# MotionerController.net
KiCad netlist of a schematic drawn in EAGLE
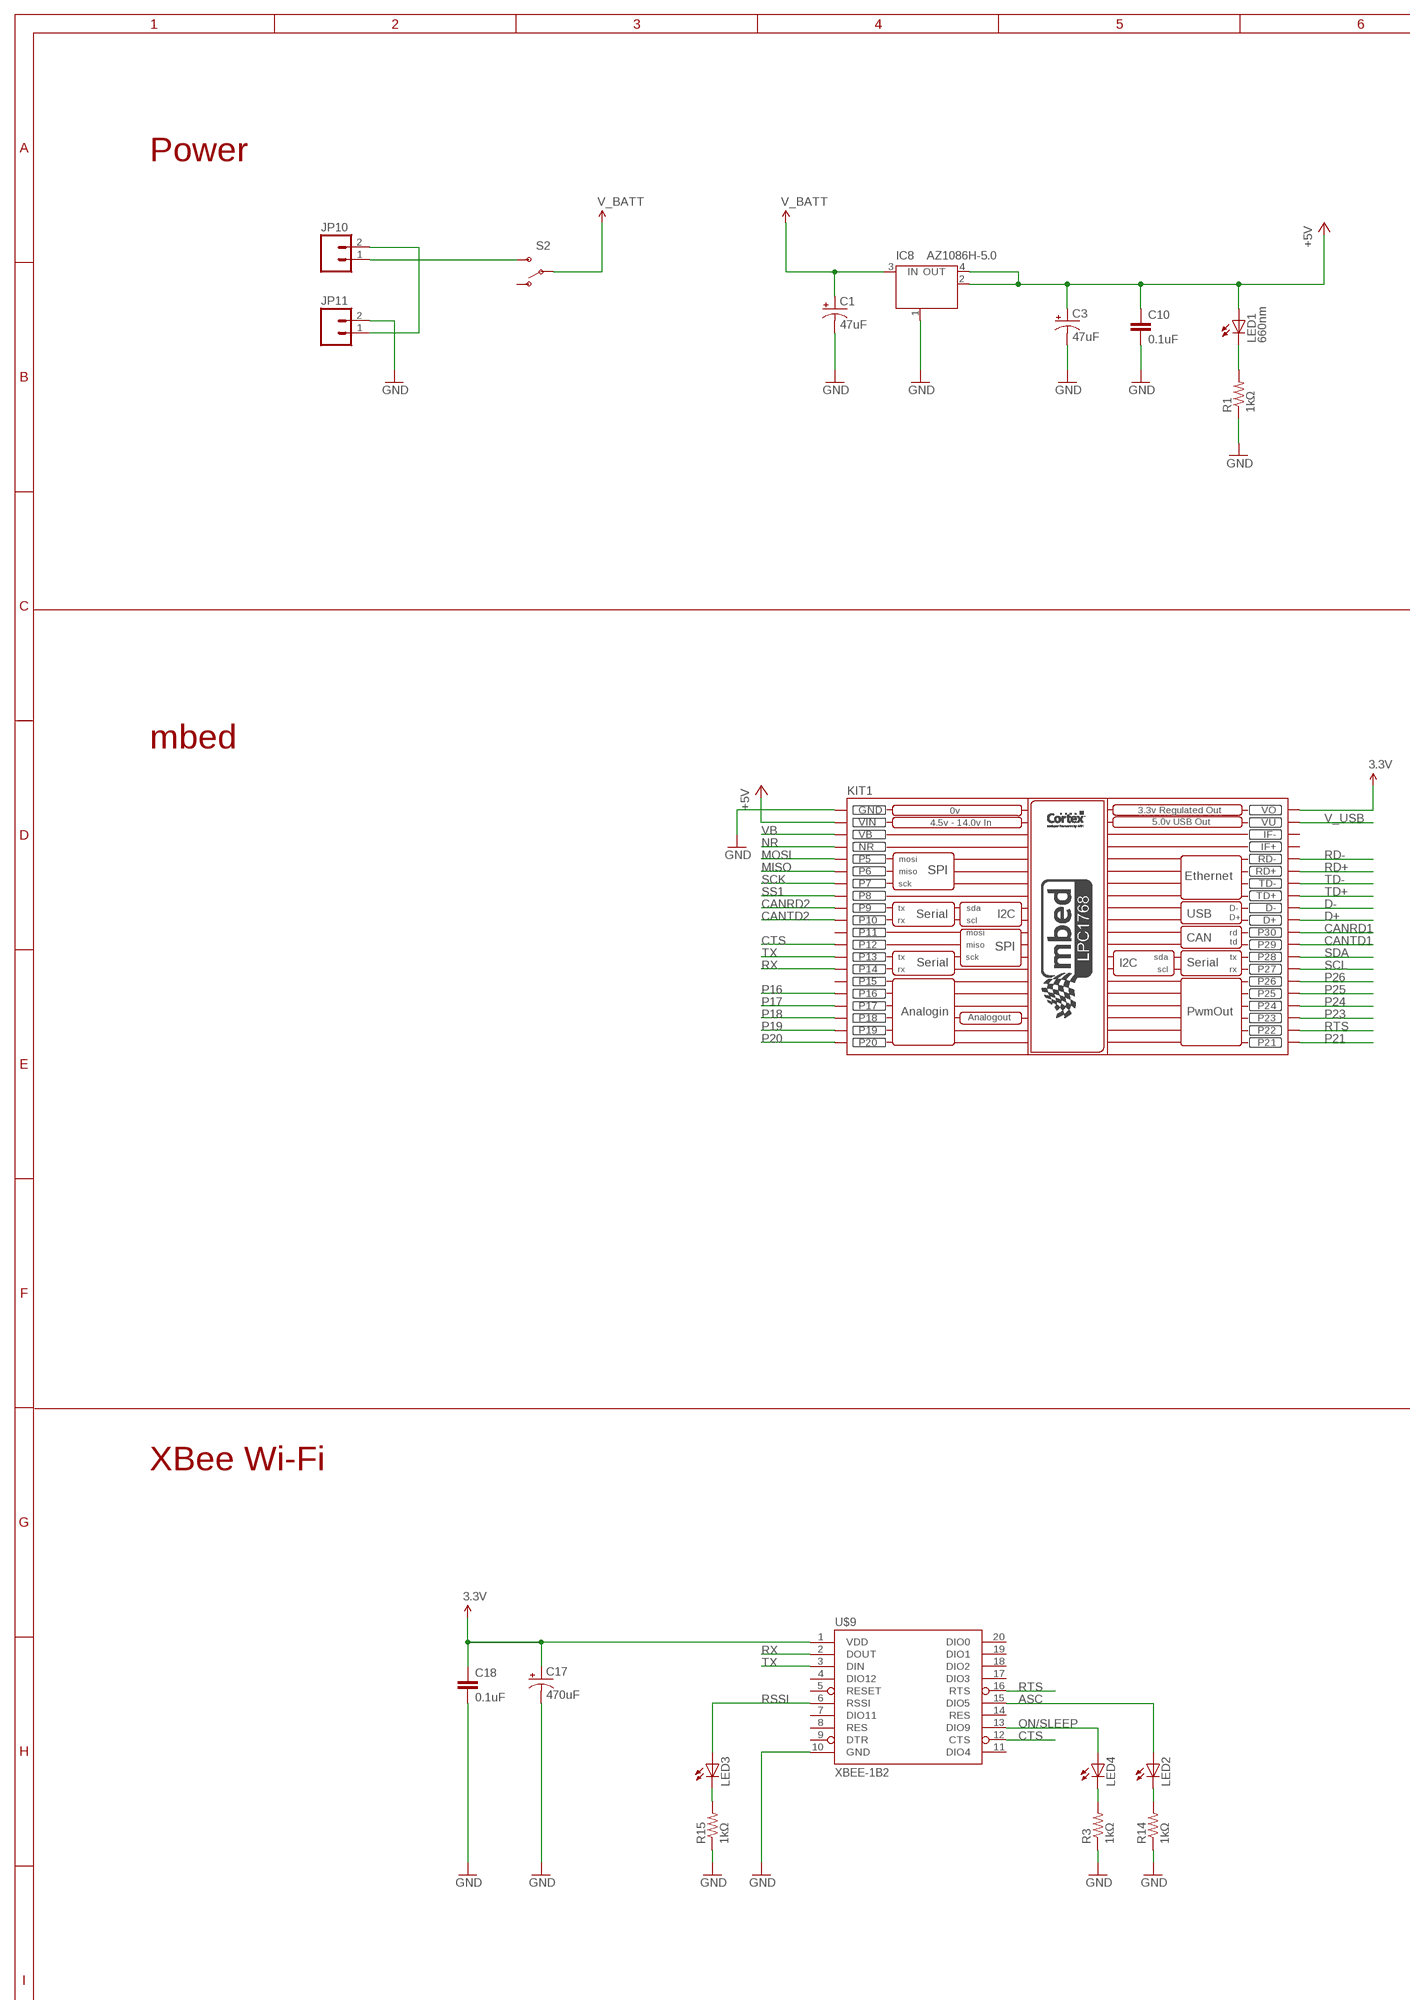
[diagram p0: schematic, sheet 1, part 1 of 2]
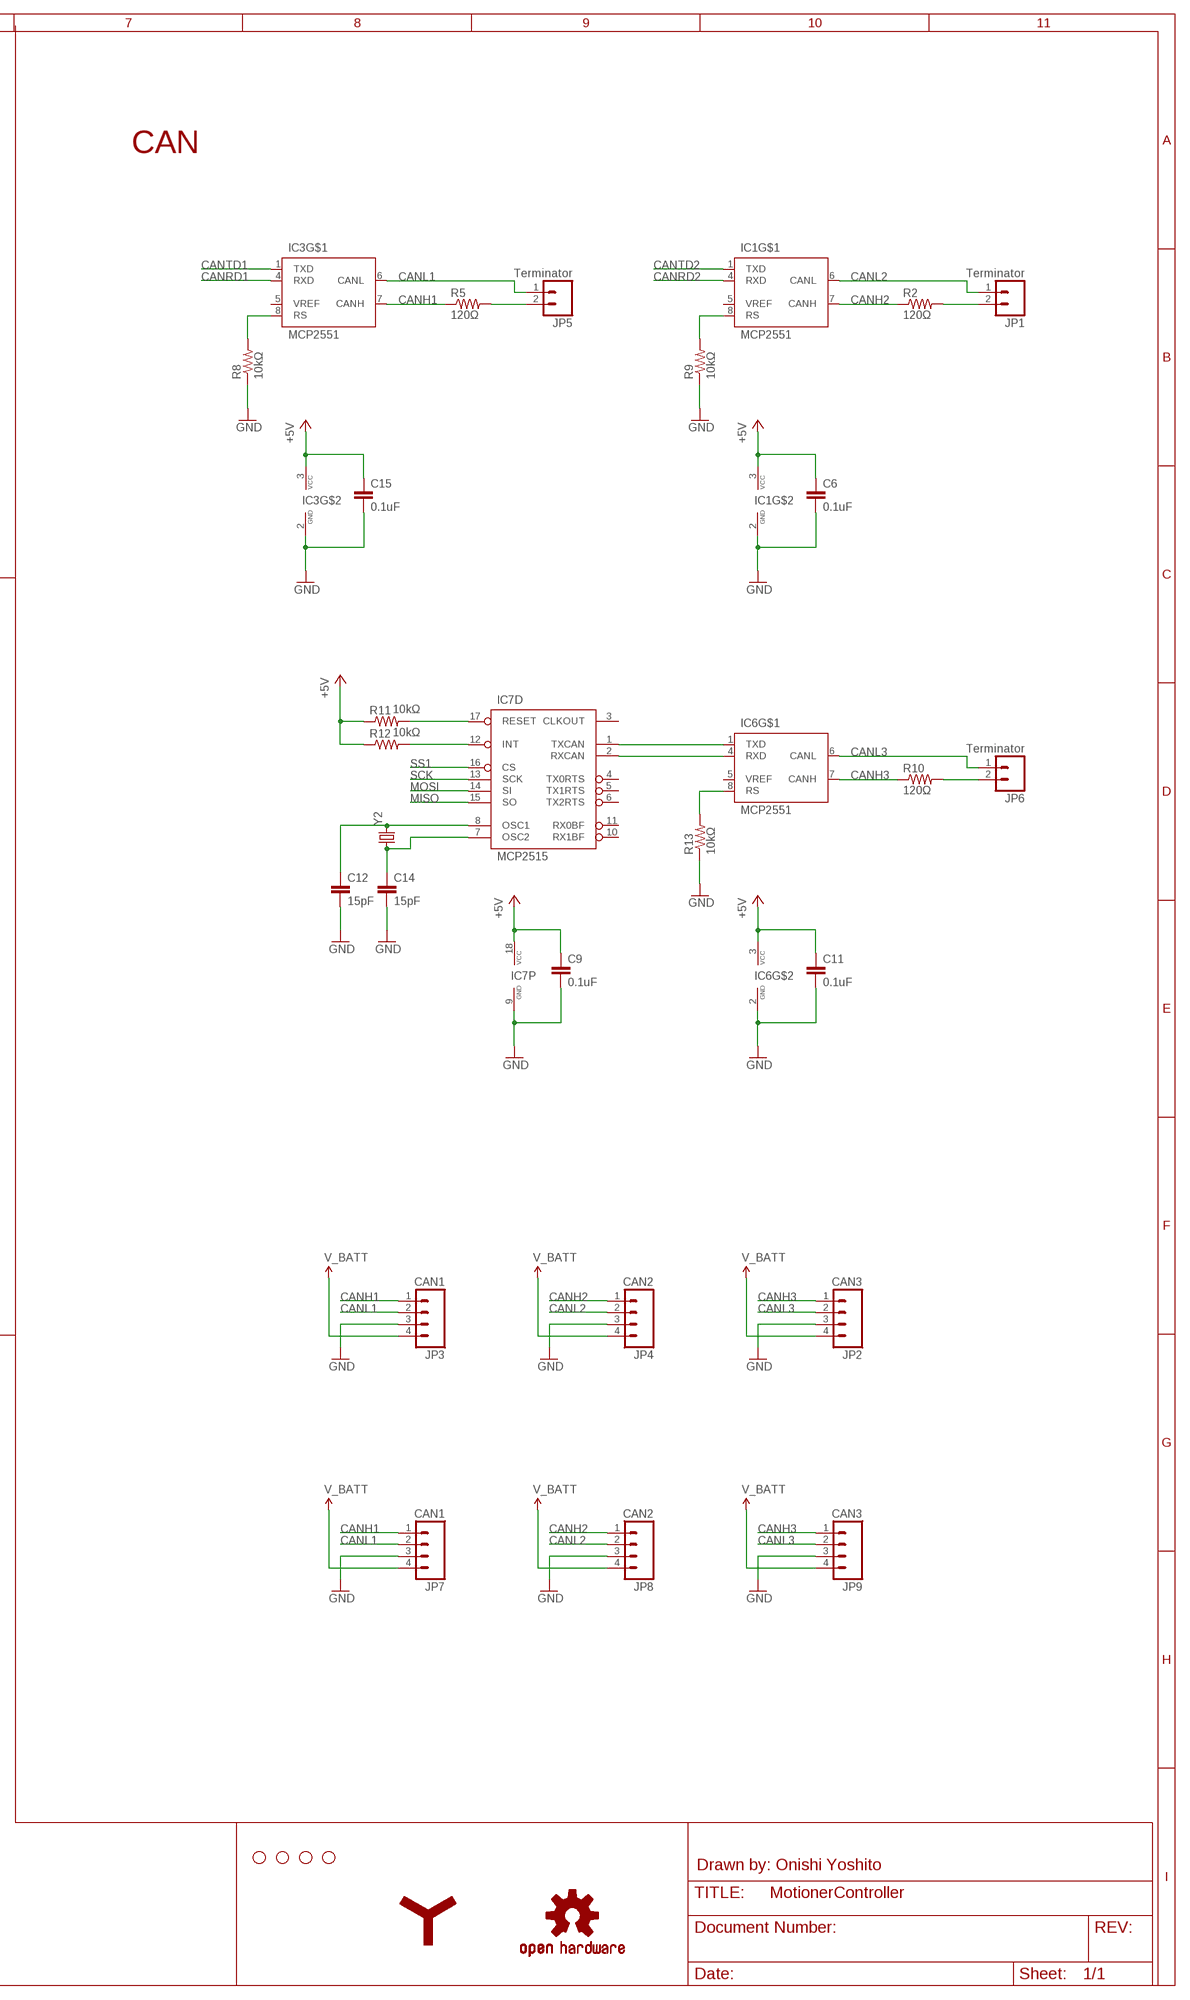
[diagram p1: schematic, sheet 1, part 2 of 2]

(export (version "E")
  (design (tool "Eeschema 10.0.6"))
  (components
    (comp (ref "C1")
      (value "47uF")
      (footprint "eagle-import:PANASONIC_D")
      (libsource (lib "eagle-import") (part "CAP_POLD"))
    )
    (comp (ref "C3")
      (value "47uF")
      (footprint "eagle-import:PANASONIC_D")
      (libsource (lib "eagle-import") (part "CAP_POLD"))
    )
    (comp (ref "C6")
      (value "0.1uF")
      (footprint "eagle-import:0603-CAP")
      (libsource (lib "eagle-import") (part "CAP0603-CAP"))
    )
    (comp (ref "C9")
      (value "0.1uF")
      (footprint "eagle-import:0603-CAP")
      (libsource (lib "eagle-import") (part "CAP0603-CAP"))
    )
    (comp (ref "C10")
      (value "0.1uF")
      (footprint "eagle-import:0603-CAP")
      (libsource (lib "eagle-import") (part "CAP0603-CAP"))
    )
    (comp (ref "C11")
      (value "0.1uF")
      (footprint "eagle-import:0603-CAP")
      (libsource (lib "eagle-import") (part "CAP0603-CAP"))
    )
    (comp (ref "C12")
      (value "15pF")
      (footprint "eagle-import:0603-CAP")
      (libsource (lib "eagle-import") (part "CAP0603-CAP"))
    )
    (comp (ref "C14")
      (value "15pF")
      (footprint "eagle-import:0603-CAP")
      (libsource (lib "eagle-import") (part "CAP0603-CAP"))
    )
    (comp (ref "C15")
      (value "0.1uF")
      (footprint "eagle-import:0603-CAP")
      (libsource (lib "eagle-import") (part "CAP0603-CAP"))
    )
    (comp (ref "C17")
      (value "470uF")
      (footprint "eagle-import:PANASONIC_G")
      (libsource (lib "eagle-import") (part "CAP_POLG"))
    )
    (comp (ref "C18")
      (value "0.1uF")
      (footprint "eagle-import:0603-CAP")
      (libsource (lib "eagle-import") (part "CAP0603-CAP"))
    )
    (comp (ref "IC1")
      (value "MCP2551")
      (footprint "eagle-import:SO08")
      (libsource (lib "eagle-import") (part "MCP2551SO8"))
    )
    (comp (ref "IC3")
      (value "MCP2551")
      (footprint "eagle-import:SO08")
      (libsource (lib "eagle-import") (part "MCP2551SO8"))
    )
    (comp (ref "IC6")
      (value "MCP2551")
      (footprint "eagle-import:SO08")
      (libsource (lib "eagle-import") (part "MCP2551SO8"))
    )
    (comp (ref "IC7")
      (value "MCP2515")
      (footprint "eagle-import:SO-18W")
      (libsource (lib "eagle-import") (part "MCP2515SO"))
    )
    (comp (ref "IC8")
      (value "AZ1086H-5.0")
      (footprint "eagle-import:SOT223")
      (libsource (lib "eagle-import") (part "MC33269ST-3.3T3"))
    )
    (comp (ref "JP1")
      (value "Terminator")
      (footprint "eagle-import:1X02")
      (libsource (lib "eagle-import") (part "M02PTH"))
    )
    (comp (ref "JP2")
      (value "CAN3")
      (footprint "eagle-import:JST-4-PTH")
      (libsource (lib "eagle-import") (part "M04JST-PTH"))
    )
    (comp (ref "JP3")
      (value "CAN1")
      (footprint "eagle-import:JST-4-PTH")
      (libsource (lib "eagle-import") (part "M04JST-PTH"))
    )
    (comp (ref "JP4")
      (value "CAN2")
      (footprint "eagle-import:JST-4-PTH")
      (libsource (lib "eagle-import") (part "M04JST-PTH"))
    )
    (comp (ref "JP5")
      (value "Terminator")
      (footprint "eagle-import:1X02")
      (libsource (lib "eagle-import") (part "M02PTH"))
    )
    (comp (ref "JP6")
      (value "Terminator")
      (footprint "eagle-import:1X02")
      (libsource (lib "eagle-import") (part "M02PTH"))
    )
    (comp (ref "JP7")
      (value "CAN1")
      (footprint "eagle-import:JST-4-PTH")
      (libsource (lib "eagle-import") (part "M04JST-PTH"))
    )
    (comp (ref "JP8")
      (value "CAN2")
      (footprint "eagle-import:JST-4-PTH")
      (libsource (lib "eagle-import") (part "M04JST-PTH"))
    )
    (comp (ref "JP9")
      (value "CAN3")
      (footprint "eagle-import:JST-4-PTH")
      (libsource (lib "eagle-import") (part "M04JST-PTH"))
    )
    (comp (ref "JP10")
      (value "M02JST-PTH-2")
      (footprint "eagle-import:JST-2-PTH")
      (libsource (lib "eagle-import") (part "M02JST-PTH-2"))
    )
    (comp (ref "JP11")
      (value "M02JST-PTH-2")
      (footprint "eagle-import:JST-2-PTH")
      (libsource (lib "eagle-import") (part "M02JST-PTH-2"))
    )
    (comp (ref "JP12")
      (value "STAND-OFF")
      (footprint "eagle-import:STAND-OFF")
      (libsource (lib "eagle-import") (part "STAND-OFF"))
    )
    (comp (ref "JP13")
      (value "STAND-OFF")
      (footprint "eagle-import:STAND-OFF")
      (libsource (lib "eagle-import") (part "STAND-OFF"))
    )
    (comp (ref "JP15")
      (value "STAND-OFF")
      (footprint "eagle-import:STAND-OFF")
      (libsource (lib "eagle-import") (part "STAND-OFF"))
    )
    (comp (ref "JP16")
      (value "STAND-OFF")
      (footprint "eagle-import:STAND-OFF")
      (libsource (lib "eagle-import") (part "STAND-OFF"))
    )
    (comp (ref "KIT1")
      (value "MBED_NXP_LPC1768")
      (footprint "eagle-import:MBED-KIT")
      (libsource (lib "eagle-import") (part "MBED_NXP_LPC1768"))
    )
    (comp (ref "LED1")
      (value "660nm")
      (footprint "eagle-import:LED-0603")
      (libsource (lib "eagle-import") (part "LED0603"))
    )
    (comp (ref "LED2")
      (value "LED0603")
      (footprint "eagle-import:LED-0603")
      (libsource (lib "eagle-import") (part "LED0603"))
    )
    (comp (ref "LED3")
      (value "LED0603")
      (footprint "eagle-import:LED-0603")
      (libsource (lib "eagle-import") (part "LED0603"))
    )
    (comp (ref "LED4")
      (value "LED0603")
      (footprint "eagle-import:LED-0603")
      (libsource (lib "eagle-import") (part "LED0603"))
    )
    (comp (ref "R1")
      (value "1kΩ")
      (footprint "eagle-import:0603-RES")
      (libsource (lib "eagle-import") (part "RESISTOR0603-RES"))
    )
    (comp (ref "R2")
      (value "120Ω")
      (footprint "eagle-import:0603-RES")
      (libsource (lib "eagle-import") (part "RESISTOR0603-RES"))
    )
    (comp (ref "R3")
      (value "1kΩ")
      (footprint "eagle-import:0603-RES")
      (libsource (lib "eagle-import") (part "RESISTOR0603-RES"))
    )
    (comp (ref "R5")
      (value "120Ω")
      (footprint "eagle-import:0603-RES")
      (libsource (lib "eagle-import") (part "RESISTOR0603-RES"))
    )
    (comp (ref "R8")
      (value "10kΩ")
      (footprint "eagle-import:0603-RES")
      (libsource (lib "eagle-import") (part "RESISTOR0603-RES"))
    )
    (comp (ref "R9")
      (value "10kΩ")
      (footprint "eagle-import:0603-RES")
      (libsource (lib "eagle-import") (part "RESISTOR0603-RES"))
    )
    (comp (ref "R10")
      (value "120Ω")
      (footprint "eagle-import:0603-RES")
      (libsource (lib "eagle-import") (part "RESISTOR0603-RES"))
    )
    (comp (ref "R11")
      (value "10kΩ")
      (footprint "eagle-import:0603-RES")
      (libsource (lib "eagle-import") (part "RESISTOR0603-RES"))
    )
    (comp (ref "R12")
      (value "10kΩ")
      (footprint "eagle-import:0603-RES")
      (libsource (lib "eagle-import") (part "RESISTOR0603-RES"))
    )
    (comp (ref "R13")
      (value "10kΩ")
      (footprint "eagle-import:0603-RES")
      (libsource (lib "eagle-import") (part "RESISTOR0603-RES"))
    )
    (comp (ref "R14")
      (value "1kΩ")
      (footprint "eagle-import:0603-RES")
      (libsource (lib "eagle-import") (part "RESISTOR0603-RES"))
    )
    (comp (ref "R15")
      (value "1kΩ")
      (footprint "eagle-import:0603-RES")
      (libsource (lib "eagle-import") (part "RESISTOR0603-RES"))
    )
    (comp (ref "S2")
      (value "SWITCH-SPDTPTH")
      (footprint "eagle-import:SWITCH-SPDT")
      (libsource (lib "eagle-import") (part "SWITCH-SPDTPTH"))
    )
    (comp (ref "U$9")
      (value "XBEE-1B2")
      (footprint "eagle-import:XBEE-SILK")
      (libsource (lib "eagle-import") (part "XBEE-1B2"))
    )
    (comp (ref "U$10")
      (value "YCAM_LOGO_L")
      (footprint "eagle-import:YCAM_LOGO_L")
      (libsource (lib "eagle-import") (part "YCAM_LOGO_L"))
    )
    (comp (ref "U$12")
      (value "OSHW-LOGOL")
      (footprint "eagle-import:OSHW-LOGO-L")
      (libsource (lib "eagle-import") (part "OSHW-LOGOL"))
    )
    (comp (ref "Y2")
      (value "CRYSTAL5X3")
      (footprint "eagle-import:CRYSTAL-SMD-5X3")
      (libsource (lib "eagle-import") (part "CRYSTAL5X3"))
    )
  )
  (nets
    (net (code "1") (name "+5V") (class "Default")
      (node (ref "C10") (pin "1") (pinfunction "1_1") (pintype "passive"))
      (node (ref "C11") (pin "1") (pinfunction "1_1") (pintype "passive"))
      (node (ref "C15") (pin "1") (pinfunction "1_1") (pintype "passive"))
      (node (ref "C3") (pin "+") (pinfunction "+_+") (pintype "passive"))
      (node (ref "C6") (pin "1") (pinfunction "1_1") (pintype "passive"))
      (node (ref "C9") (pin "1") (pinfunction "1_1") (pintype "passive"))
      (node (ref "IC1") (pin "3") (pinfunction "VCC_3") (pintype "power_in"))
      (node (ref "IC3") (pin "3") (pinfunction "VCC_3") (pintype "power_in"))
      (node (ref "IC6") (pin "3") (pinfunction "VCC_3") (pintype "power_in"))
      (node (ref "IC7") (pin "18") (pinfunction "VCC_18") (pintype "power_in"))
      (node (ref "IC8") (pin "2") (pinfunction "OUT_2") (pintype "passive"))
      (node (ref "IC8") (pin "4") (pinfunction "OUT_4") (pintype "passive"))
      (node (ref "KIT1") (pin "VIN") (pinfunction "VIN_VIN") (pintype "power_in"))
      (node (ref "LED1") (pin "A") (pinfunction "A_A") (pintype "passive"))
      (node (ref "R11") (pin "1") (pinfunction "1_1") (pintype "passive"))
      (node (ref "R12") (pin "1") (pinfunction "1_1") (pintype "passive"))
    )
    (net (code "2") (name "/ASC") (class "Default")
      (node (ref "LED2") (pin "A") (pinfunction "A_A") (pintype "passive"))
      (node (ref "U$9") (pin "15") (pinfunction "DIO5_15") (pintype "bidirectional"))
    )
    (net (code "3") (name "/CANH1") (class "Default")
      (node (ref "IC3") (pin "7") (pinfunction "CANH_7") (pintype "bidirectional"))
      (node (ref "JP3") (pin "1") (pinfunction "1_1") (pintype "passive"))
      (node (ref "JP7") (pin "1") (pinfunction "1_1") (pintype "passive"))
      (node (ref "R5") (pin "1") (pinfunction "1_1") (pintype "passive"))
    )
    (net (code "4") (name "/CANH2") (class "Default")
      (node (ref "IC1") (pin "7") (pinfunction "CANH_7") (pintype "bidirectional"))
      (node (ref "JP4") (pin "1") (pinfunction "1_1") (pintype "passive"))
      (node (ref "JP8") (pin "1") (pinfunction "1_1") (pintype "passive"))
      (node (ref "R2") (pin "1") (pinfunction "1_1") (pintype "passive"))
    )
    (net (code "5") (name "/CANH3") (class "Default")
      (node (ref "IC6") (pin "7") (pinfunction "CANH_7") (pintype "bidirectional"))
      (node (ref "JP2") (pin "1") (pinfunction "1_1") (pintype "passive"))
      (node (ref "JP9") (pin "1") (pinfunction "1_1") (pintype "passive"))
      (node (ref "R10") (pin "1") (pinfunction "1_1") (pintype "passive"))
    )
    (net (code "6") (name "/CANL1") (class "Default")
      (node (ref "IC3") (pin "6") (pinfunction "CANL_6") (pintype "bidirectional"))
      (node (ref "JP3") (pin "2") (pinfunction "2_2") (pintype "passive"))
      (node (ref "JP5") (pin "1") (pinfunction "1_1") (pintype "passive"))
      (node (ref "JP7") (pin "2") (pinfunction "2_2") (pintype "passive"))
    )
    (net (code "7") (name "/CANL2") (class "Default")
      (node (ref "IC1") (pin "6") (pinfunction "CANL_6") (pintype "bidirectional"))
      (node (ref "JP1") (pin "1") (pinfunction "1_1") (pintype "passive"))
      (node (ref "JP4") (pin "2") (pinfunction "2_2") (pintype "passive"))
      (node (ref "JP8") (pin "2") (pinfunction "2_2") (pintype "passive"))
    )
    (net (code "8") (name "/CANL3") (class "Default")
      (node (ref "IC6") (pin "6") (pinfunction "CANL_6") (pintype "bidirectional"))
      (node (ref "JP2") (pin "2") (pinfunction "2_2") (pintype "passive"))
      (node (ref "JP6") (pin "1") (pinfunction "1_1") (pintype "passive"))
      (node (ref "JP9") (pin "2") (pinfunction "2_2") (pintype "passive"))
    )
    (net (code "9") (name "/CANRD1") (class "Default")
      (node (ref "IC3") (pin "4") (pinfunction "RXD_4") (pintype "bidirectional"))
      (node (ref "KIT1") (pin "P$30") (pinfunction "P30_P$30") (pintype "bidirectional"))
    )
    (net (code "10") (name "/CANRD2") (class "Default")
      (node (ref "IC1") (pin "4") (pinfunction "RXD_4") (pintype "bidirectional"))
      (node (ref "KIT1") (pin "P$9") (pinfunction "P9_P$9") (pintype "bidirectional"))
    )
    (net (code "11") (name "/CANTD1") (class "Default")
      (node (ref "IC3") (pin "1") (pinfunction "TXD_1") (pintype "bidirectional"))
      (node (ref "KIT1") (pin "P$29") (pinfunction "P29_P$29") (pintype "bidirectional"))
    )
    (net (code "12") (name "/CANTD2") (class "Default")
      (node (ref "IC1") (pin "1") (pinfunction "TXD_1") (pintype "bidirectional"))
      (node (ref "KIT1") (pin "P$10") (pinfunction "P10_P$10") (pintype "bidirectional"))
    )
    (net (code "13") (name "/CTS") (class "Default")
      (node (ref "KIT1") (pin "P$12") (pinfunction "P12_P$12") (pintype "bidirectional"))
      (node (ref "U$9") (pin "12") (pinfunction "CTS_12") (pintype "output"))
    )
    (net (code "14") (name "/D+") (class "Default")
      (node (ref "KIT1") (pin "D+") (pinfunction "D+_D+") (pintype "bidirectional"))
    )
    (net (code "15") (name "/D-") (class "Default")
      (node (ref "KIT1") (pin "D-") (pinfunction "D-_D-") (pintype "bidirectional"))
    )
    (net (code "16") (name "/MISO") (class "Default")
      (node (ref "IC7") (pin "15") (pinfunction "SO_15") (pintype "output"))
      (node (ref "KIT1") (pin "P$6") (pinfunction "P6_P$6") (pintype "bidirectional"))
    )
    (net (code "17") (name "/MOSI") (class "Default")
      (node (ref "IC7") (pin "14") (pinfunction "SI_14") (pintype "input"))
      (node (ref "KIT1") (pin "P$5") (pinfunction "P5_P$5") (pintype "bidirectional"))
    )
    (net (code "18") (name "/NR") (class "Default")
      (node (ref "KIT1") (pin "NR") (pinfunction "NR_NR") (pintype "power_in"))
    )
    (net (code "19") (name "/ON{slash}SLEEP") (class "Default")
      (node (ref "LED4") (pin "A") (pinfunction "A_A") (pintype "passive"))
      (node (ref "U$9") (pin "13") (pinfunction "DIO9_13") (pintype "bidirectional"))
    )
    (net (code "20") (name "/P16") (class "Default")
      (node (ref "KIT1") (pin "P$16") (pinfunction "P16_P$16") (pintype "bidirectional"))
    )
    (net (code "21") (name "/P17") (class "Default")
      (node (ref "KIT1") (pin "P$17") (pinfunction "P17_P$17") (pintype "bidirectional"))
    )
    (net (code "22") (name "/P18") (class "Default")
      (node (ref "KIT1") (pin "P$18") (pinfunction "P18_P$18") (pintype "bidirectional"))
    )
    (net (code "23") (name "/P19") (class "Default")
      (node (ref "KIT1") (pin "P$19") (pinfunction "P19_P$19") (pintype "bidirectional"))
    )
    (net (code "24") (name "/P20") (class "Default")
      (node (ref "KIT1") (pin "P$20") (pinfunction "P20_P$20") (pintype "bidirectional"))
    )
    (net (code "25") (name "/P21") (class "Default")
      (node (ref "KIT1") (pin "P$21") (pinfunction "P21_P$21") (pintype "bidirectional"))
    )
    (net (code "26") (name "/P23") (class "Default")
      (node (ref "KIT1") (pin "P$23") (pinfunction "P23_P$23") (pintype "bidirectional"))
    )
    (net (code "27") (name "/P24") (class "Default")
      (node (ref "KIT1") (pin "P$24") (pinfunction "P24_P$24") (pintype "bidirectional"))
    )
    (net (code "28") (name "/P25") (class "Default")
      (node (ref "KIT1") (pin "P$25") (pinfunction "P25_P$25") (pintype "bidirectional"))
    )
    (net (code "29") (name "/P26") (class "Default")
      (node (ref "KIT1") (pin "P$26") (pinfunction "P26_P$26") (pintype "bidirectional"))
    )
    (net (code "30") (name "/RD+") (class "Default")
      (node (ref "KIT1") (pin "RD+") (pinfunction "RD+_RD+") (pintype "bidirectional"))
    )
    (net (code "31") (name "/RD-") (class "Default")
      (node (ref "KIT1") (pin "RD-") (pinfunction "RD-_RD-") (pintype "bidirectional"))
    )
    (net (code "32") (name "/RSSI") (class "Default")
      (node (ref "LED3") (pin "A") (pinfunction "A_A") (pintype "passive"))
      (node (ref "U$9") (pin "6") (pinfunction "RSSI_6") (pintype "bidirectional"))
    )
    (net (code "33") (name "/RTS") (class "Default")
      (node (ref "KIT1") (pin "P$22") (pinfunction "P22_P$22") (pintype "bidirectional"))
      (node (ref "U$9") (pin "16") (pinfunction "RTS_16") (pintype "input"))
    )
    (net (code "34") (name "/RX") (class "Default")
      (node (ref "KIT1") (pin "P$14") (pinfunction "P14_P$14") (pintype "bidirectional"))
      (node (ref "U$9") (pin "2") (pinfunction "DOUT_2") (pintype "output"))
    )
    (net (code "35") (name "/SCK") (class "Default")
      (node (ref "IC7") (pin "13") (pinfunction "SCK_13") (pintype "input"))
      (node (ref "KIT1") (pin "P$7") (pinfunction "P7_P$7") (pintype "bidirectional"))
    )
    (net (code "36") (name "/SCL") (class "Default")
      (node (ref "KIT1") (pin "P$27") (pinfunction "P27_P$27") (pintype "bidirectional"))
    )
    (net (code "37") (name "/SDA") (class "Default")
      (node (ref "KIT1") (pin "P$28") (pinfunction "P28_P$28") (pintype "bidirectional"))
    )
    (net (code "38") (name "/SS1") (class "Default")
      (node (ref "IC7") (pin "16") (pinfunction "CS_16") (pintype "input"))
      (node (ref "KIT1") (pin "P$8") (pinfunction "P8_P$8") (pintype "bidirectional"))
    )
    (net (code "39") (name "/TD+") (class "Default")
      (node (ref "KIT1") (pin "TD+") (pinfunction "TD+_TD+") (pintype "bidirectional"))
    )
    (net (code "40") (name "/TD-") (class "Default")
      (node (ref "KIT1") (pin "TD-") (pinfunction "TD-_TD-") (pintype "bidirectional"))
    )
    (net (code "41") (name "/TX") (class "Default")
      (node (ref "KIT1") (pin "P$13") (pinfunction "P13_P$13") (pintype "bidirectional"))
      (node (ref "U$9") (pin "3") (pinfunction "DIN_3") (pintype "input"))
    )
    (net (code "42") (name "/VB") (class "Default")
      (node (ref "KIT1") (pin "VB") (pinfunction "VB_VB") (pintype "power_in"))
    )
    (net (code "43") (name "/V_USB") (class "Default")
      (node (ref "KIT1") (pin "VU") (pinfunction "VU_VU") (pintype "power_in"))
    )
    (net (code "44") (name "3.3V") (class "Default")
      (node (ref "C17") (pin "+") (pinfunction "+_+") (pintype "passive"))
      (node (ref "C18") (pin "1") (pinfunction "1_1") (pintype "passive"))
      (node (ref "KIT1") (pin "VOUT") (pinfunction "VO_VOUT") (pintype "power_in"))
      (node (ref "U$9") (pin "1") (pinfunction "VDD_1") (pintype "power_in"))
    )
    (net (code "45") (name "GND") (class "Default")
      (node (ref "C1") (pin "-") (pinfunction "-_-") (pintype "passive"))
      (node (ref "C10") (pin "2") (pinfunction "2_2") (pintype "passive"))
      (node (ref "C11") (pin "2") (pinfunction "2_2") (pintype "passive"))
      (node (ref "C12") (pin "2") (pinfunction "2_2") (pintype "passive"))
      (node (ref "C14") (pin "2") (pinfunction "2_2") (pintype "passive"))
      (node (ref "C15") (pin "2") (pinfunction "2_2") (pintype "passive"))
      (node (ref "C17") (pin "-") (pinfunction "-_-") (pintype "passive"))
      (node (ref "C18") (pin "2") (pinfunction "2_2") (pintype "passive"))
      (node (ref "C3") (pin "-") (pinfunction "-_-") (pintype "passive"))
      (node (ref "C6") (pin "2") (pinfunction "2_2") (pintype "passive"))
      (node (ref "C9") (pin "2") (pinfunction "2_2") (pintype "passive"))
      (node (ref "IC1") (pin "2") (pinfunction "GND_2") (pintype "power_in"))
      (node (ref "IC3") (pin "2") (pinfunction "GND_2") (pintype "power_in"))
      (node (ref "IC6") (pin "2") (pinfunction "GND_2") (pintype "power_in"))
      (node (ref "IC7") (pin "9") (pinfunction "GND_9") (pintype "power_in"))
      (node (ref "IC8") (pin "1") (pinfunction "GND/ADJ_1") (pintype "input"))
      (node (ref "JP11") (pin "2") (pinfunction "2_2") (pintype "passive"))
      (node (ref "JP2") (pin "3") (pinfunction "3_3") (pintype "passive"))
      (node (ref "JP3") (pin "3") (pinfunction "3_3") (pintype "passive"))
      (node (ref "JP4") (pin "3") (pinfunction "3_3") (pintype "passive"))
      (node (ref "JP7") (pin "3") (pinfunction "3_3") (pintype "passive"))
      (node (ref "JP8") (pin "3") (pinfunction "3_3") (pintype "passive"))
      (node (ref "JP9") (pin "3") (pinfunction "3_3") (pintype "passive"))
      (node (ref "KIT1") (pin "GND") (pinfunction "GND_GND") (pintype "power_in"))
      (node (ref "R1") (pin "1") (pinfunction "1_1") (pintype "passive"))
      (node (ref "R13") (pin "1") (pinfunction "1_1") (pintype "passive"))
      (node (ref "R14") (pin "1") (pinfunction "1_1") (pintype "passive"))
      (node (ref "R15") (pin "1") (pinfunction "1_1") (pintype "passive"))
      (node (ref "R3") (pin "1") (pinfunction "1_1") (pintype "passive"))
      (node (ref "R8") (pin "1") (pinfunction "1_1") (pintype "passive"))
      (node (ref "R9") (pin "1") (pinfunction "1_1") (pintype "passive"))
      (node (ref "U$9") (pin "10") (pinfunction "GND_10") (pintype "power_in"))
    )
    (net (code "46") (name "Net-(IC1A-RS)") (class "Default")
      (node (ref "IC1") (pin "8") (pinfunction "RS_8") (pintype "bidirectional"))
      (node (ref "R9") (pin "2") (pinfunction "2_2") (pintype "passive"))
    )
    (net (code "47") (name "Net-(IC3A-RS)") (class "Default")
      (node (ref "IC3") (pin "8") (pinfunction "RS_8") (pintype "bidirectional"))
      (node (ref "R8") (pin "2") (pinfunction "2_2") (pintype "passive"))
    )
    (net (code "48") (name "Net-(IC6A-RS)") (class "Default")
      (node (ref "IC6") (pin "8") (pinfunction "RS_8") (pintype "bidirectional"))
      (node (ref "R13") (pin "2") (pinfunction "2_2") (pintype "passive"))
    )
    (net (code "49") (name "Net-(IC6A-RXD)") (class "Default")
      (node (ref "IC6") (pin "4") (pinfunction "RXD_4") (pintype "bidirectional"))
      (node (ref "IC7") (pin "2") (pinfunction "RXCAN_2") (pintype "input"))
    )
    (net (code "50") (name "Net-(IC6A-TXD)") (class "Default")
      (node (ref "IC6") (pin "1") (pinfunction "TXD_1") (pintype "bidirectional"))
      (node (ref "IC7") (pin "1") (pinfunction "TXCAN_1") (pintype "output"))
    )
    (net (code "51") (name "Net-(IC7A-INT)") (class "Default")
      (node (ref "IC7") (pin "12") (pinfunction "INT_12") (pintype "output"))
      (node (ref "R12") (pin "2") (pinfunction "2_2") (pintype "passive"))
    )
    (net (code "52") (name "Net-(IC7A-OSC1)") (class "Default")
      (node (ref "C12") (pin "1") (pinfunction "1_1") (pintype "passive"))
      (node (ref "IC7") (pin "8") (pinfunction "OSC1_8") (pintype "input"))
      (node (ref "Y2") (pin "3") (pinfunction "2_3") (pintype "passive"))
    )
    (net (code "53") (name "Net-(IC7A-OSC2)") (class "Default")
      (node (ref "C14") (pin "1") (pinfunction "1_1") (pintype "passive"))
      (node (ref "IC7") (pin "7") (pinfunction "OSC2_7") (pintype "input"))
      (node (ref "Y2") (pin "1") (pinfunction "1_1") (pintype "passive"))
    )
    (net (code "54") (name "Net-(IC7A-RESET)") (class "Default")
      (node (ref "IC7") (pin "17") (pinfunction "RESET_17") (pintype "input"))
      (node (ref "R11") (pin "2") (pinfunction "2_2") (pintype "passive"))
    )
    (net (code "55") (name "Net-(JP1-Pad2)") (class "Default")
      (node (ref "JP1") (pin "2") (pinfunction "2_2") (pintype "passive"))
      (node (ref "R2") (pin "2") (pinfunction "2_2") (pintype "passive"))
    )
    (net (code "56") (name "Net-(JP5-Pad2)") (class "Default")
      (node (ref "JP5") (pin "2") (pinfunction "2_2") (pintype "passive"))
      (node (ref "R5") (pin "2") (pinfunction "2_2") (pintype "passive"))
    )
    (net (code "57") (name "Net-(JP6-Pad2)") (class "Default")
      (node (ref "JP6") (pin "2") (pinfunction "2_2") (pintype "passive"))
      (node (ref "R10") (pin "2") (pinfunction "2_2") (pintype "passive"))
    )
    (net (code "58") (name "Net-(JP10-Pad2)") (class "Default")
      (node (ref "JP10") (pin "2") (pinfunction "2_2") (pintype "passive"))
      (node (ref "JP11") (pin "1") (pinfunction "1_1") (pintype "passive"))
    )
    (net (code "59") (name "Net-(LED1-PadC)") (class "Default")
      (node (ref "LED1") (pin "C") (pinfunction "C_C") (pintype "passive"))
      (node (ref "R1") (pin "2") (pinfunction "2_2") (pintype "passive"))
    )
    (net (code "60") (name "Net-(LED2-PadC)") (class "Default")
      (node (ref "LED2") (pin "C") (pinfunction "C_C") (pintype "passive"))
      (node (ref "R14") (pin "2") (pinfunction "2_2") (pintype "passive"))
    )
    (net (code "61") (name "Net-(LED3-PadC)") (class "Default")
      (node (ref "LED3") (pin "C") (pinfunction "C_C") (pintype "passive"))
      (node (ref "R15") (pin "2") (pinfunction "2_2") (pintype "passive"))
    )
    (net (code "62") (name "Net-(LED4-PadC)") (class "Default")
      (node (ref "LED4") (pin "C") (pinfunction "C_C") (pintype "passive"))
      (node (ref "R3") (pin "2") (pinfunction "2_2") (pintype "passive"))
    )
    (net (code "63") (name "Net-(S2-S)") (class "Default")
      (node (ref "JP10") (pin "1") (pinfunction "1_1") (pintype "passive"))
      (node (ref "S2") (pin "3") (pinfunction "S_3") (pintype "passive"))
    )
    (net (code "64") (name "V_BATT") (class "Default")
      (node (ref "C1") (pin "+") (pinfunction "+_+") (pintype "passive"))
      (node (ref "IC8") (pin "3") (pinfunction "IN_3") (pintype "input"))
      (node (ref "JP2") (pin "4") (pinfunction "4_4") (pintype "passive"))
      (node (ref "JP3") (pin "4") (pinfunction "4_4") (pintype "passive"))
      (node (ref "JP4") (pin "4") (pinfunction "4_4") (pintype "passive"))
      (node (ref "JP7") (pin "4") (pinfunction "4_4") (pintype "passive"))
      (node (ref "JP8") (pin "4") (pinfunction "4_4") (pintype "passive"))
      (node (ref "JP9") (pin "4") (pinfunction "4_4") (pintype "passive"))
      (node (ref "S2") (pin "2") (pinfunction "P_2") (pintype "passive"))
    )
    (net (code "65") (name "unconnected-(IC1A-VREF-Pad5)") (class "Default")
      (node (ref "IC1") (pin "5") (pinfunction "VREF_5") (pintype "bidirectional"))
    )
    (net (code "66") (name "unconnected-(IC3A-VREF-Pad5)") (class "Default")
      (node (ref "IC3") (pin "5") (pinfunction "VREF_5") (pintype "bidirectional"))
    )
    (net (code "67") (name "unconnected-(IC6A-VREF-Pad5)") (class "Default")
      (node (ref "IC6") (pin "5") (pinfunction "VREF_5") (pintype "bidirectional"))
    )
    (net (code "68") (name "unconnected-(IC7A-CLKOUT-Pad3)") (class "Default")
      (node (ref "IC7") (pin "3") (pinfunction "CLKOUT_3") (pintype "output"))
    )
    (net (code "69") (name "unconnected-(IC7A-RX0BF-Pad11)") (class "Default")
      (node (ref "IC7") (pin "11") (pinfunction "RX0BF_11") (pintype "output"))
    )
    (net (code "70") (name "unconnected-(IC7A-RX1BF-Pad10)") (class "Default")
      (node (ref "IC7") (pin "10") (pinfunction "RX1BF_10") (pintype "output"))
    )
    (net (code "71") (name "unconnected-(IC7A-TX0RTS-Pad4)") (class "Default")
      (node (ref "IC7") (pin "4") (pinfunction "TX0RTS_4") (pintype "input"))
    )
    (net (code "72") (name "unconnected-(IC7A-TX1RTS-Pad5)") (class "Default")
      (node (ref "IC7") (pin "5") (pinfunction "TX1RTS_5") (pintype "input"))
    )
    (net (code "73") (name "unconnected-(IC7A-TX2RTS-Pad6)") (class "Default")
      (node (ref "IC7") (pin "6") (pinfunction "TX2RTS_6") (pintype "input"))
    )
    (net (code "74") (name "unconnected-(KIT1-P11-PadP$11)") (class "Default")
      (node (ref "KIT1") (pin "P$11") (pinfunction "P11_P$11") (pintype "bidirectional"))
    )
    (net (code "75") (name "unconnected-(KIT1-P15-PadP$15)") (class "Default")
      (node (ref "KIT1") (pin "P$15") (pinfunction "P15_P$15") (pintype "bidirectional"))
    )
    (net (code "76") (name "unconnected-(KIT1-PadIF+)") (class "Default")
      (node (ref "KIT1") (pin "IF+") (pinfunction "IF+_IF+") (pintype "bidirectional"))
    )
    (net (code "77") (name "unconnected-(KIT1-PadIF-)") (class "Default")
      (node (ref "KIT1") (pin "IF-") (pinfunction "IF-_IF-") (pintype "bidirectional"))
    )
    (net (code "78") (name "unconnected-(S2-O-Pad1)") (class "Default")
      (node (ref "S2") (pin "1") (pinfunction "O_1") (pintype "passive"))
    )
    (net (code "79") (name "unconnected-(U$9-DIO0-Pad20)") (class "Default")
      (node (ref "U$9") (pin "20") (pinfunction "DIO0_20") (pintype "bidirectional"))
    )
    (net (code "80") (name "unconnected-(U$9-DIO1-Pad19)") (class "Default")
      (node (ref "U$9") (pin "19") (pinfunction "DIO1_19") (pintype "bidirectional"))
    )
    (net (code "81") (name "unconnected-(U$9-DIO2-Pad18)") (class "Default")
      (node (ref "U$9") (pin "18") (pinfunction "DIO2_18") (pintype "bidirectional"))
    )
    (net (code "82") (name "unconnected-(U$9-DIO3-Pad17)") (class "Default")
      (node (ref "U$9") (pin "17") (pinfunction "DIO3_17") (pintype "bidirectional"))
    )
    (net (code "83") (name "unconnected-(U$9-DIO4-Pad11)") (class "Default")
      (node (ref "U$9") (pin "11") (pinfunction "DIO4_11") (pintype "bidirectional"))
    )
    (net (code "84") (name "unconnected-(U$9-DIO11-Pad7)") (class "Default")
      (node (ref "U$9") (pin "7") (pinfunction "DIO11_7") (pintype "bidirectional"))
    )
    (net (code "85") (name "unconnected-(U$9-DIO12-Pad4)") (class "Default")
      (node (ref "U$9") (pin "4") (pinfunction "DIO12_4") (pintype "bidirectional"))
    )
    (net (code "86") (name "unconnected-(U$9-DTR-Pad9)") (class "Default")
      (node (ref "U$9") (pin "9") (pinfunction "DTR_9") (pintype "bidirectional"))
    )
    (net (code "87") (name "unconnected-(U$9-RES-Pad8)") (class "Default")
      (node (ref "U$9") (pin "8") (pinfunction "RES_8") (pintype "bidirectional"))
    )
    (net (code "88") (name "unconnected-(U$9-RES-Pad14)") (class "Default")
      (node (ref "U$9") (pin "14") (pinfunction "RES_14") (pintype "bidirectional"))
    )
    (net (code "89") (name "unconnected-(U$9-RESET-Pad5)") (class "Default")
      (node (ref "U$9") (pin "5") (pinfunction "RESET_5") (pintype "input"))
    )
  )
)
